# norbi_lm_pl_dcr.net
KiCad netlist of a schematic drawn in Altium Designer
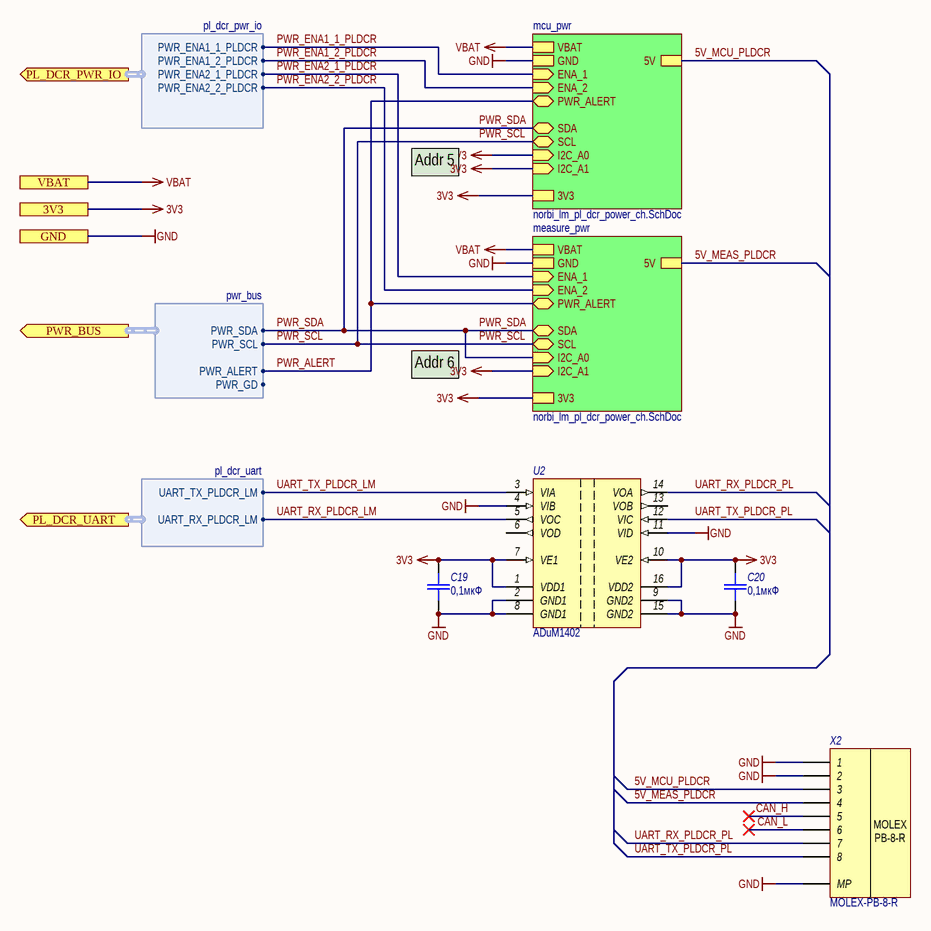
[diagram p0: norbi_lm_pl_dcr.SchDoc]

(export (version "E")
  (design (tool "Eeschema 10.0.6"))
  (components
    (comp (ref "C19")
      (value "0,1мкФ")
      (footprint "CR-0805")
      (description "Конденсатор для поверхностного монтажа")
      (libsource (lib "my_passive") (part "C_smd"))
    )
    (comp (ref "C20")
      (value "0,1мкФ")
      (footprint "CR-0805")
      (description "Конденсатор для поверхностного монтажа")
      (libsource (lib "my_passive") (part "C_smd"))
    )
    (comp (ref "U2")
      (value "ADuM1402")
      (footprint "SOIC-16-WIDE")
      (description "Quad Channel Digital Isolator, 2.5 KV rms Insulation Rating")
      (fields (field (name "НАИМЕНОВАНИЕ") "ADuM1402"))
      (libsource (lib "my_integrated_circuit") (part "ADuM1402"))
    )
    (comp (ref "X2")
      (value "MOLEX-PB-8")
      (footprint "MOLEX-PB-8-R")
      (description "MOLEX PicoBlade 8-pin")
      (fields (field (name "НАИМЕНОВАНИЕ") "MOLEX-PB-8-R"))
      (libsource (lib "my_connector") (part "MOLEX-PB-8"))
    )
  )
  (nets
    (net (code "4") (name "/5V_MCU_PLDCR") (class "Default")
      (node (ref "X2") (pin "3") (pinfunction "3_3") (pintype "passive"))
    )
    (net (code "5") (name "/5V_MEAS_PLDCR") (class "Default")
      (node (ref "X2") (pin "4") (pinfunction "4_4") (pintype "passive"))
    )
    (net (code "6") (name "/CAN_H") (class "Default")
      (node (ref "X2") (pin "5") (pinfunction "5_5") (pintype "passive+no_connect"))
    )
    (net (code "7") (name "/CAN_L") (class "Default")
      (node (ref "X2") (pin "6") (pinfunction "6_6") (pintype "passive+no_connect"))
    )
    (net (code "15") (name "/UART_RX_PLDCR_LM") (class "Default")
      (node (ref "U2") (pin "5") (pinfunction "VOC_5") (pintype "output"))
    )
    (net (code "16") (name "/UART_RX_PLDCR_PL") (class "Default")
      (node (ref "U2") (pin "14") (pinfunction "VOA_14") (pintype "output"))
      (node (ref "X2") (pin "7") (pinfunction "7_7") (pintype "passive"))
    )
    (net (code "17") (name "/UART_TX_PLDCR_LM") (class "Default")
      (node (ref "U2") (pin "3") (pinfunction "VIA_3") (pintype "input"))
    )
    (net (code "18") (name "/UART_TX_PLDCR_PL") (class "Default")
      (node (ref "U2") (pin "12") (pinfunction "VIC_12") (pintype "input"))
      (node (ref "X2") (pin "8") (pinfunction "8_8") (pintype "passive"))
    )
    (net (code "22") (name "3V3") (class "Default")
      (node (ref "C19") (pin "2") (pinfunction "2_2") (pintype "passive"))
      (node (ref "C20") (pin "2") (pinfunction "2_2") (pintype "passive"))
      (node (ref "U2") (pin "1") (pinfunction "VDD1_1") (pintype "power_in"))
      (node (ref "U2") (pin "10") (pinfunction "VE2_10") (pintype "input"))
      (node (ref "U2") (pin "16") (pinfunction "VDD2_16") (pintype "power_in"))
      (node (ref "U2") (pin "7") (pinfunction "VE1_7") (pintype "input"))
    )
    (net (code "23") (name "GND") (class "Default")
      (node (ref "C19") (pin "1") (pinfunction "1_1") (pintype "passive"))
      (node (ref "C20") (pin "1") (pinfunction "1_1") (pintype "passive"))
      (node (ref "U2") (pin "11") (pinfunction "VID_11") (pintype "input"))
      (node (ref "U2") (pin "15") (pinfunction "GND2_15") (pintype "power_in"))
      (node (ref "U2") (pin "2") (pinfunction "GND1_2") (pintype "power_in"))
      (node (ref "U2") (pin "4") (pinfunction "VIB_4") (pintype "input"))
      (node (ref "U2") (pin "8") (pinfunction "GND1_8") (pintype "power_in"))
      (node (ref "U2") (pin "9") (pinfunction "GND2_9") (pintype "power_in"))
      (node (ref "X2") (pin "1") (pinfunction "1_1") (pintype "passive"))
      (node (ref "X2") (pin "2") (pinfunction "2_2") (pintype "passive"))
      (node (ref "X2") (pin "MP") (pinfunction "MP_MP") (pintype "passive"))
    )
    (net (code "25") (name "unconnected-(U2-VOB-Pad13)") (class "Default")
      (node (ref "U2") (pin "13") (pinfunction "VOB_13") (pintype "output"))
    )
    (net (code "26") (name "unconnected-(U2-VOD-Pad6)") (class "Default")
      (node (ref "U2") (pin "6") (pinfunction "VOD_6") (pintype "output"))
    )
  )
)
